# TSOC_CYBLE_R0_1.net
KiCad netlist of a schematic drawn in EAGLE
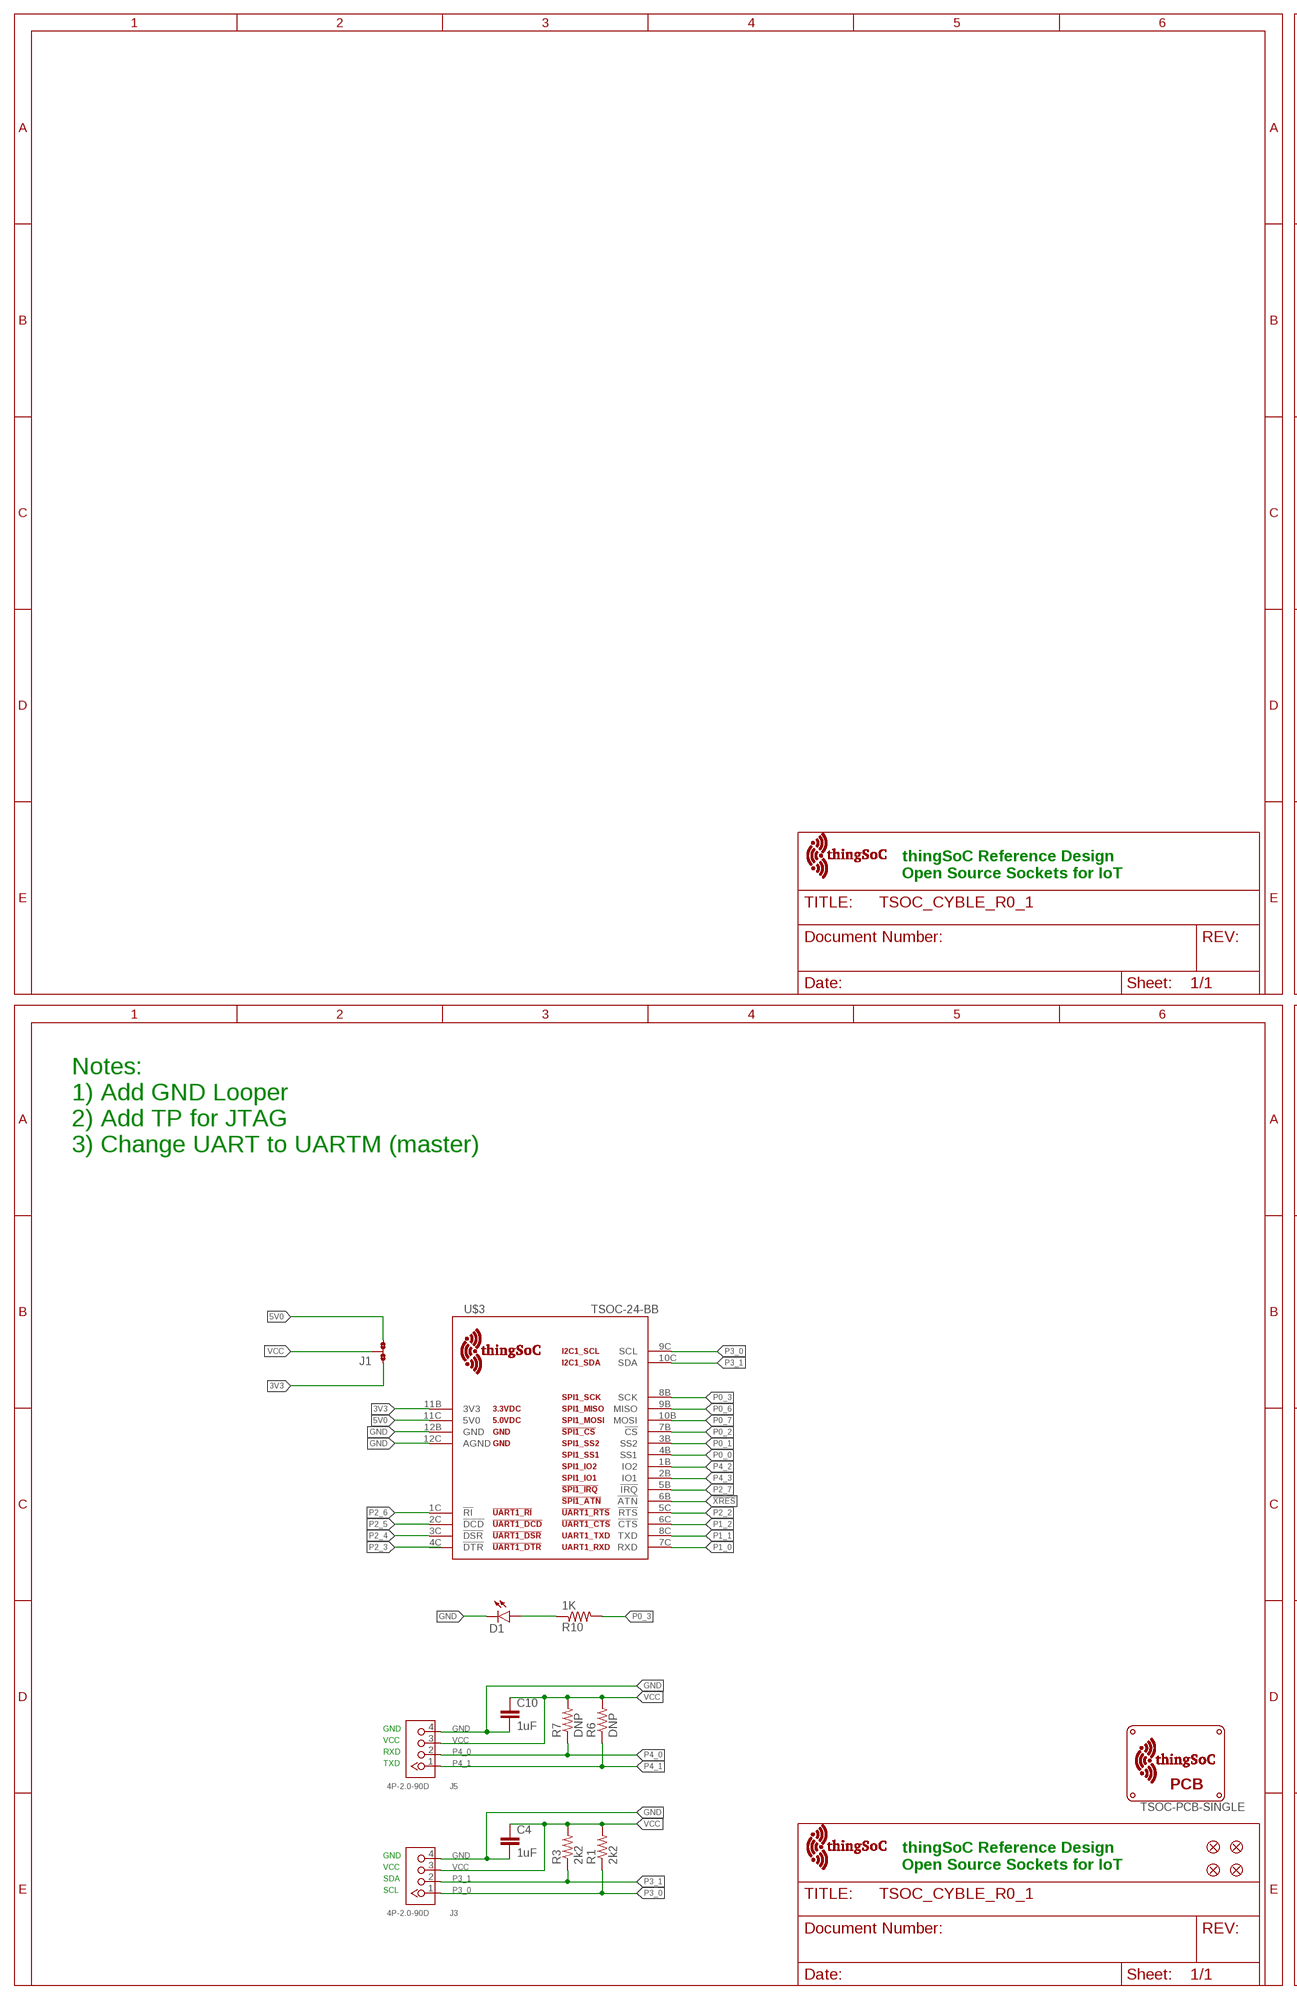
[diagram p0: schematic, sheet 1, part 1 of 2]
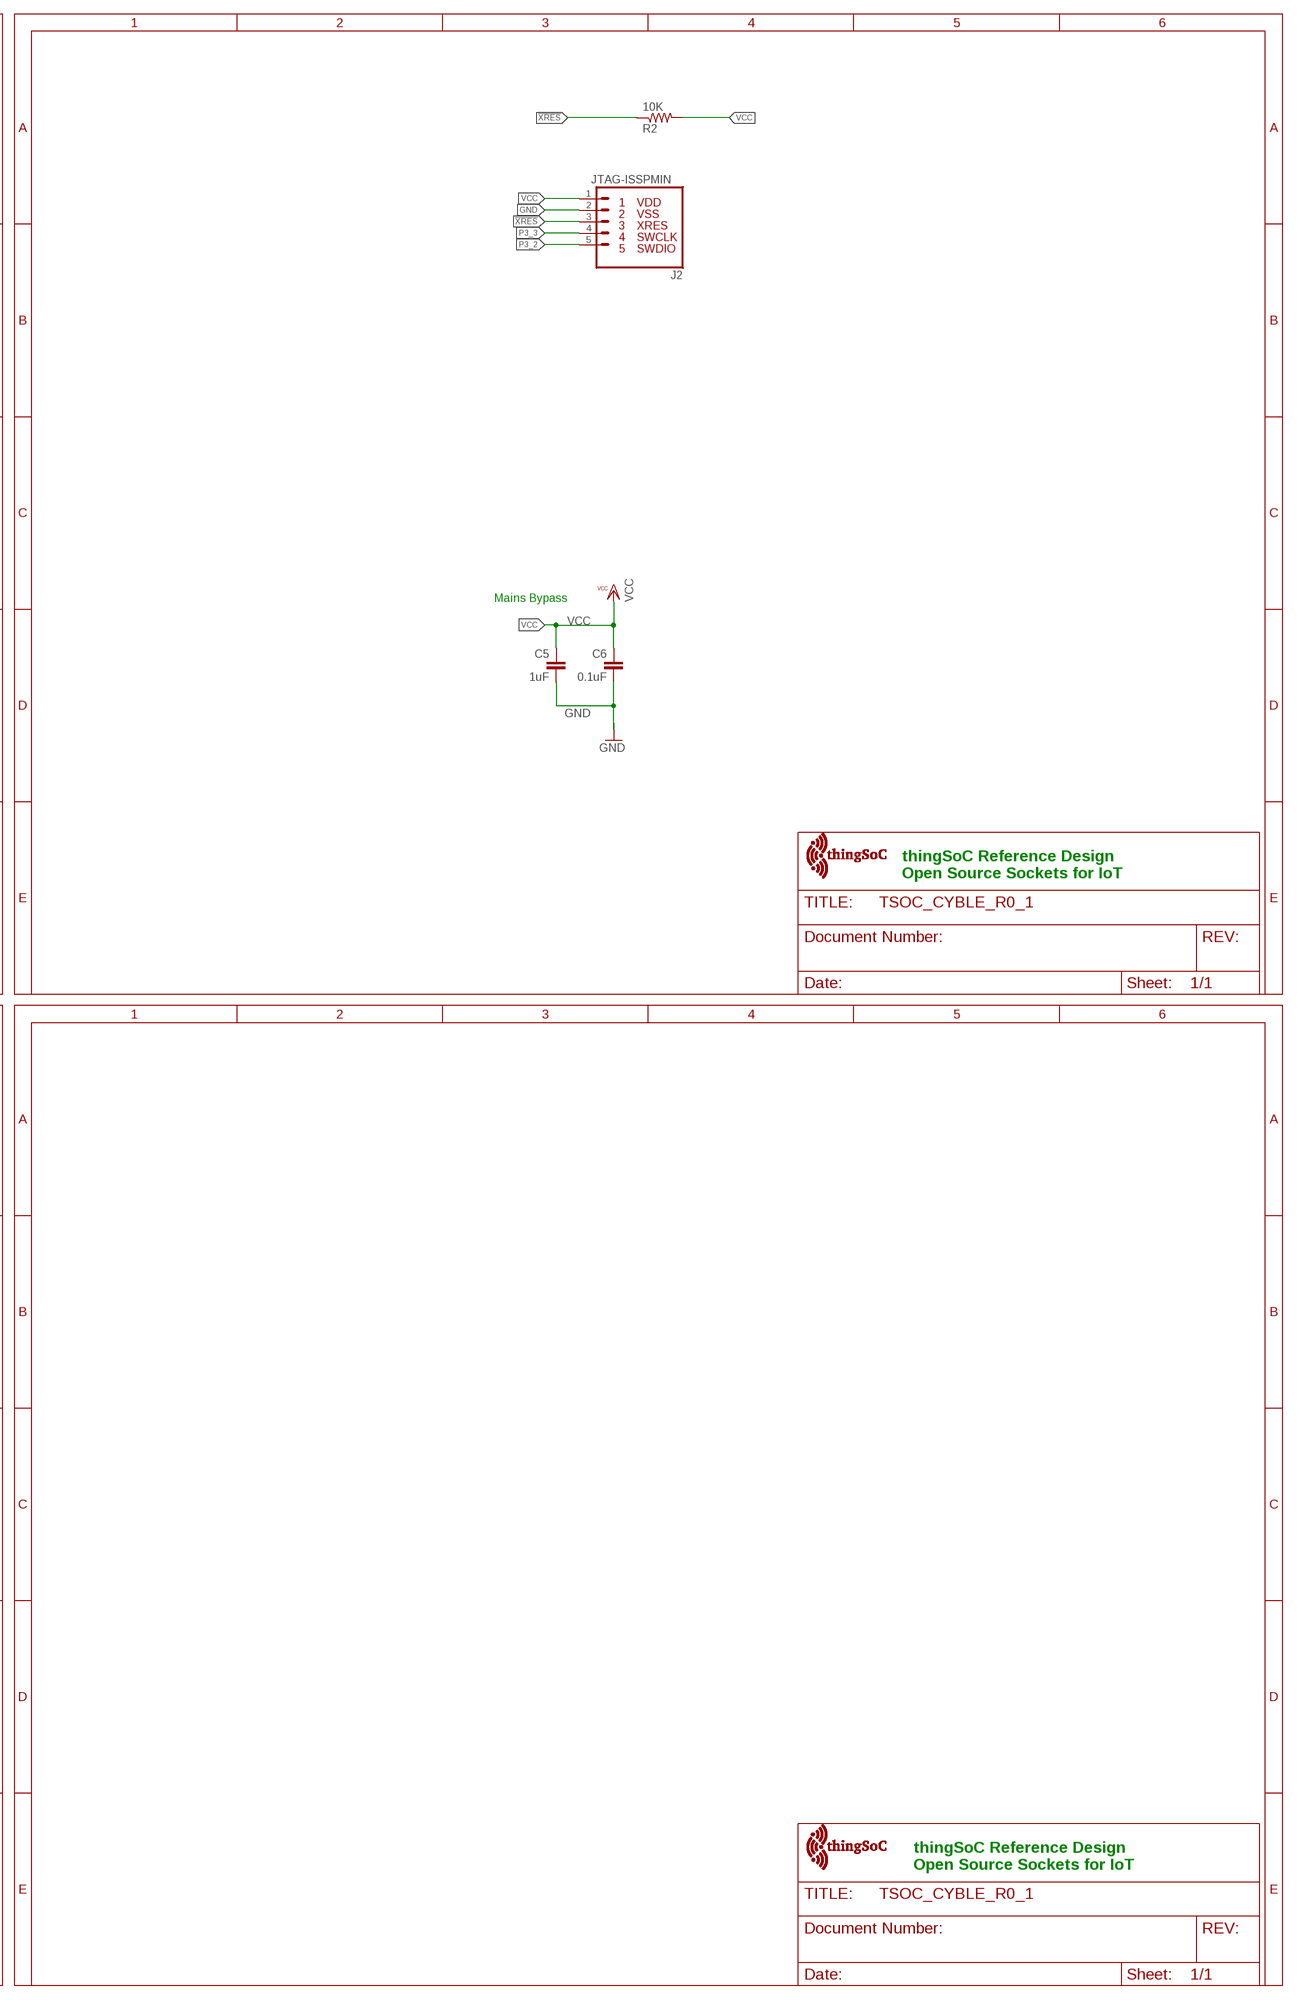
[diagram p1: schematic, sheet 1, part 2 of 2]

(export (version "E")
  (design (tool "Eeschema 10.0.6"))
  (components
    (comp (ref "C4")
      (value "1uF")
      (footprint "eagle-import:0603-CAP")
      (libsource (lib "eagle-import") (part "SparkFun-Passives_CAP0603-CAP"))
    )
    (comp (ref "C5")
      (value "1uF")
      (footprint "eagle-import:0603-CAP")
      (libsource (lib "eagle-import") (part "CAP0603-CAP"))
    )
    (comp (ref "C6")
      (value "0.1uF")
      (footprint "eagle-import:0603-CAP")
      (libsource (lib "eagle-import") (part "CAP0603-CAP"))
    )
    (comp (ref "C10")
      (value "1uF")
      (footprint "eagle-import:0603-CAP")
      (libsource (lib "eagle-import") (part "SparkFun-Passives_CAP0603-CAP"))
    )
    (comp (ref "D1")
      (value "LED0603")
      (footprint "eagle-import:LED-0603")
      (libsource (lib "eagle-import") (part "LED0603"))
    )
    (comp (ref "FID1")
      (value "FIDUCIALUFIDUCIAL")
      (footprint "eagle-import:MICRO-FIDUCIAL")
      (libsource (lib "eagle-import") (part "FIDUCIALUFIDUCIAL"))
    )
    (comp (ref "FID2")
      (value "FIDUCIALUFIDUCIAL")
      (footprint "eagle-import:MICRO-FIDUCIAL")
      (libsource (lib "eagle-import") (part "FIDUCIALUFIDUCIAL"))
    )
    (comp (ref "FID3")
      (value "FIDUCIALUFIDUCIAL")
      (footprint "eagle-import:MICRO-FIDUCIAL")
      (libsource (lib "eagle-import") (part "FIDUCIALUFIDUCIAL"))
    )
    (comp (ref "FID4")
      (value "FIDUCIALUFIDUCIAL")
      (footprint "eagle-import:MICRO-FIDUCIAL")
      (libsource (lib "eagle-import") (part "FIDUCIALUFIDUCIAL"))
    )
    (comp (ref "J1")
      (value "JMP-3-NO-PTH")
      (footprint "eagle-import:JMP-3-NO-PTH-2.54")
      (libsource (lib "eagle-import") (part "JMP-3-NO-PTH"))
    )
    (comp (ref "J2")
      (value "JTAG-ISSPMIN")
      (footprint "eagle-import:PSOC_JTAG_MINSILK")
      (libsource (lib "eagle-import") (part "JTAG-ISSPMIN"))
    )
    (comp (ref "J3")
      (value "4P-2.0-90D")
      (footprint "eagle-import:HW4-2.0-90D")
      (libsource (lib "eagle-import") (part "GROVE-CONNECTOR-DIP-90D(4P-2.0)"))
    )
    (comp (ref "J5")
      (value "4P-2.0-90D")
      (footprint "eagle-import:HW4-2.0-90D")
      (libsource (lib "eagle-import") (part "GROVE-CONNECTOR-DIP-90D(4P-2.0)"))
    )
    (comp (ref "R1")
      (value "2k2")
      (footprint "eagle-import:0603-RES")
      (libsource (lib "eagle-import") (part "RESISTOR0603-RES"))
    )
    (comp (ref "R2")
      (value "10K")
      (footprint "eagle-import:0603-RES")
      (libsource (lib "eagle-import") (part "RESISTOR_SFE0603-RES"))
    )
    (comp (ref "R3")
      (value "2k2")
      (footprint "eagle-import:0603-RES")
      (libsource (lib "eagle-import") (part "RESISTOR0603-RES"))
    )
    (comp (ref "R6")
      (value "DNP")
      (footprint "eagle-import:0603-RES")
      (libsource (lib "eagle-import") (part "RESISTOR0603-RES"))
    )
    (comp (ref "R7")
      (value "DNP")
      (footprint "eagle-import:0603-RES")
      (libsource (lib "eagle-import") (part "RESISTOR0603-RES"))
    )
    (comp (ref "R10")
      (value "1K")
      (footprint "eagle-import:0603-RES")
      (libsource (lib "eagle-import") (part "RESISTOR_SFE0603-RES"))
    )
    (comp (ref "U$1")
      (value "TSOC-LOGO-MED")
      (footprint "eagle-import:TSOC-LOGO-MED")
      (libsource (lib "eagle-import") (part "TSOC-LOGO-MED"))
    )
    (comp (ref "U$2")
      (value "TSOC-PCB-SINGLE")
      (footprint "eagle-import:TSOC-BB-BRD-DIM")
      (libsource (lib "eagle-import") (part "TSOC-PCB-SINGLE"))
    )
    (comp (ref "U$3")
      (value "TSOC-24-BB")
      (footprint "eagle-import:TSOC-BB-S24")
      (libsource (lib "eagle-import") (part "TSOC-24-BB"))
    )
    (comp (ref "U$4")
      (value "TSOC-LOGO-MED")
      (footprint "eagle-import:TSOC-LOGO-MED")
      (libsource (lib "eagle-import") (part "TSOC-LOGO-MED"))
    )
    (comp (ref "U$100")
      (value "TSOC-LOGO-SMALL")
      (footprint "eagle-import:TSOC-LOGO-SML")
      (libsource (lib "eagle-import") (part "TSOC-LOGO-SMALL"))
    )
    (comp (ref "U$101")
      (value "TSOC-LOGO-LRG")
      (footprint "eagle-import:TSOC-LOGO-LRG")
      (libsource (lib "eagle-import") (part "TSOC-LOGO-LRG"))
    )
  )
  (nets
    (net (code "1") (name "/~{XRES}") (class "Default")
      (node (ref "J2") (pin "3") (pinfunction "3_3") (pintype "passive"))
      (node (ref "R2") (pin "1") (pinfunction "1_1") (pintype "passive"))
      (node (ref "U$3") (pin "6B") (pinfunction "~{ATN}_6B") (pintype "bidirectional"))
    )
    (net (code "2") (name "3V3") (class "Default")
      (node (ref "J1") (pin "1") (pinfunction "1_1") (pintype "passive"))
      (node (ref "U$3") (pin "11B") (pinfunction "3V3_11B") (pintype "bidirectional"))
    )
    (net (code "3") (name "5V0") (class "Default")
      (node (ref "J1") (pin "3") (pinfunction "3_3") (pintype "passive"))
      (node (ref "U$3") (pin "11C") (pinfunction "5V0_11C") (pintype "bidirectional"))
    )
    (net (code "4") (name "GND") (class "Default")
      (node (ref "C10") (pin "2") (pinfunction "2_2") (pintype "passive"))
      (node (ref "C4") (pin "2") (pinfunction "2_2") (pintype "passive"))
      (node (ref "C5") (pin "2") (pinfunction "2_2") (pintype "passive"))
      (node (ref "C6") (pin "2") (pinfunction "2_2") (pintype "passive"))
      (node (ref "D1") (pin "C") (pinfunction "C_C") (pintype "passive"))
      (node (ref "J2") (pin "2") (pinfunction "2_2") (pintype "passive"))
      (node (ref "J3") (pin "4") (pinfunction "4_4") (pintype "bidirectional"))
      (node (ref "J5") (pin "4") (pinfunction "4_4") (pintype "bidirectional"))
      (node (ref "U$3") (pin "12B") (pinfunction "GND_12B") (pintype "bidirectional"))
      (node (ref "U$3") (pin "12C") (pinfunction "AGND_12C") (pintype "bidirectional"))
    )
    (net (code "5") (name "Net-(D1-PadA)") (class "Default")
      (node (ref "D1") (pin "A") (pinfunction "A_A") (pintype "passive"))
      (node (ref "R10") (pin "1") (pinfunction "1_1") (pintype "passive"))
    )
    (net (code "6") (name "P0_0") (class "Default")
      (node (ref "U$3") (pin "4B") (pinfunction "SS1_4B") (pintype "bidirectional"))
    )
    (net (code "7") (name "P0_1") (class "Default")
      (node (ref "U$3") (pin "3B") (pinfunction "SS2_3B") (pintype "bidirectional"))
    )
    (net (code "8") (name "P0_2") (class "Default")
      (node (ref "U$3") (pin "7B") (pinfunction "~{CS}_7B") (pintype "bidirectional"))
    )
    (net (code "9") (name "P0_3") (class "Default")
      (node (ref "R10") (pin "2") (pinfunction "2_2") (pintype "passive"))
      (node (ref "U$3") (pin "8B") (pinfunction "SCK_8B") (pintype "bidirectional"))
    )
    (net (code "10") (name "P0_6") (class "Default")
      (node (ref "U$3") (pin "9B") (pinfunction "MISO_9B") (pintype "bidirectional"))
    )
    (net (code "11") (name "P0_7") (class "Default")
      (node (ref "U$3") (pin "10B") (pinfunction "MOSI_10B") (pintype "bidirectional"))
    )
    (net (code "12") (name "P1_0") (class "Default")
      (node (ref "U$3") (pin "7C") (pinfunction "RXD_7C") (pintype "bidirectional"))
    )
    (net (code "13") (name "P1_1") (class "Default")
      (node (ref "U$3") (pin "8C") (pinfunction "TXD_8C") (pintype "bidirectional"))
    )
    (net (code "14") (name "P1_2") (class "Default")
      (node (ref "U$3") (pin "6C") (pinfunction "~{CTS}_6C") (pintype "bidirectional"))
    )
    (net (code "15") (name "P2_2") (class "Default")
      (node (ref "U$3") (pin "5C") (pinfunction "~{RTS}_5C") (pintype "bidirectional"))
    )
    (net (code "16") (name "P2_3") (class "Default")
      (node (ref "U$3") (pin "4C") (pinfunction "~{DTR}_4C") (pintype "bidirectional"))
    )
    (net (code "17") (name "P2_4") (class "Default")
      (node (ref "U$3") (pin "3C") (pinfunction "~{DSR}_3C") (pintype "bidirectional"))
    )
    (net (code "18") (name "P2_5") (class "Default")
      (node (ref "U$3") (pin "2C") (pinfunction "~{DCD}_2C") (pintype "bidirectional"))
    )
    (net (code "19") (name "P2_6") (class "Default")
      (node (ref "U$3") (pin "1C") (pinfunction "~{RI}_1C") (pintype "bidirectional"))
    )
    (net (code "20") (name "P2_7") (class "Default")
      (node (ref "U$3") (pin "5B") (pinfunction "~{IRQ}_5B") (pintype "bidirectional"))
    )
    (net (code "21") (name "P3_0") (class "Default")
      (node (ref "J3") (pin "1") (pinfunction "1_1") (pintype "bidirectional"))
      (node (ref "R1") (pin "1") (pinfunction "1_1") (pintype "passive"))
      (node (ref "U$3") (pin "9C") (pinfunction "SCL_9C") (pintype "bidirectional"))
    )
    (net (code "22") (name "P3_1") (class "Default")
      (node (ref "J3") (pin "2") (pinfunction "2_2") (pintype "bidirectional"))
      (node (ref "R3") (pin "1") (pinfunction "1_1") (pintype "passive"))
      (node (ref "U$3") (pin "10C") (pinfunction "SDA_10C") (pintype "bidirectional"))
    )
    (net (code "23") (name "P3_2") (class "Default")
      (node (ref "J2") (pin "5") (pinfunction "5_5") (pintype "passive"))
    )
    (net (code "24") (name "P3_3") (class "Default")
      (node (ref "J2") (pin "4") (pinfunction "4_4") (pintype "passive"))
    )
    (net (code "25") (name "P4_0") (class "Default")
      (node (ref "J5") (pin "2") (pinfunction "2_2") (pintype "bidirectional"))
      (node (ref "R7") (pin "1") (pinfunction "1_1") (pintype "passive"))
    )
    (net (code "26") (name "P4_1") (class "Default")
      (node (ref "J5") (pin "1") (pinfunction "1_1") (pintype "bidirectional"))
      (node (ref "R6") (pin "1") (pinfunction "1_1") (pintype "passive"))
    )
    (net (code "27") (name "P4_2") (class "Default")
      (node (ref "U$3") (pin "1B") (pinfunction "IO2_1B") (pintype "bidirectional"))
    )
    (net (code "28") (name "P4_3") (class "Default")
      (node (ref "U$3") (pin "2B") (pinfunction "IO1_2B") (pintype "bidirectional"))
    )
    (net (code "29") (name "VCC") (class "Default")
      (node (ref "C10") (pin "1") (pinfunction "1_1") (pintype "passive"))
      (node (ref "C4") (pin "1") (pinfunction "1_1") (pintype "passive"))
      (node (ref "C5") (pin "1") (pinfunction "1_1") (pintype "passive"))
      (node (ref "C6") (pin "1") (pinfunction "1_1") (pintype "passive"))
      (node (ref "J1") (pin "2") (pinfunction "2_2") (pintype "passive"))
      (node (ref "J2") (pin "1") (pinfunction "1_1") (pintype "passive"))
      (node (ref "J3") (pin "3") (pinfunction "3_3") (pintype "bidirectional"))
      (node (ref "J5") (pin "3") (pinfunction "3_3") (pintype "bidirectional"))
      (node (ref "R1") (pin "2") (pinfunction "2_2") (pintype "passive"))
      (node (ref "R2") (pin "2") (pinfunction "2_2") (pintype "passive"))
      (node (ref "R3") (pin "2") (pinfunction "2_2") (pintype "passive"))
      (node (ref "R6") (pin "2") (pinfunction "2_2") (pintype "passive"))
      (node (ref "R7") (pin "2") (pinfunction "2_2") (pintype "passive"))
    )
  )
)
